# SCH_MONITORING-BANJIR_2024-11-29.net
KiCad netlist of a schematic drawn in EasyEDA
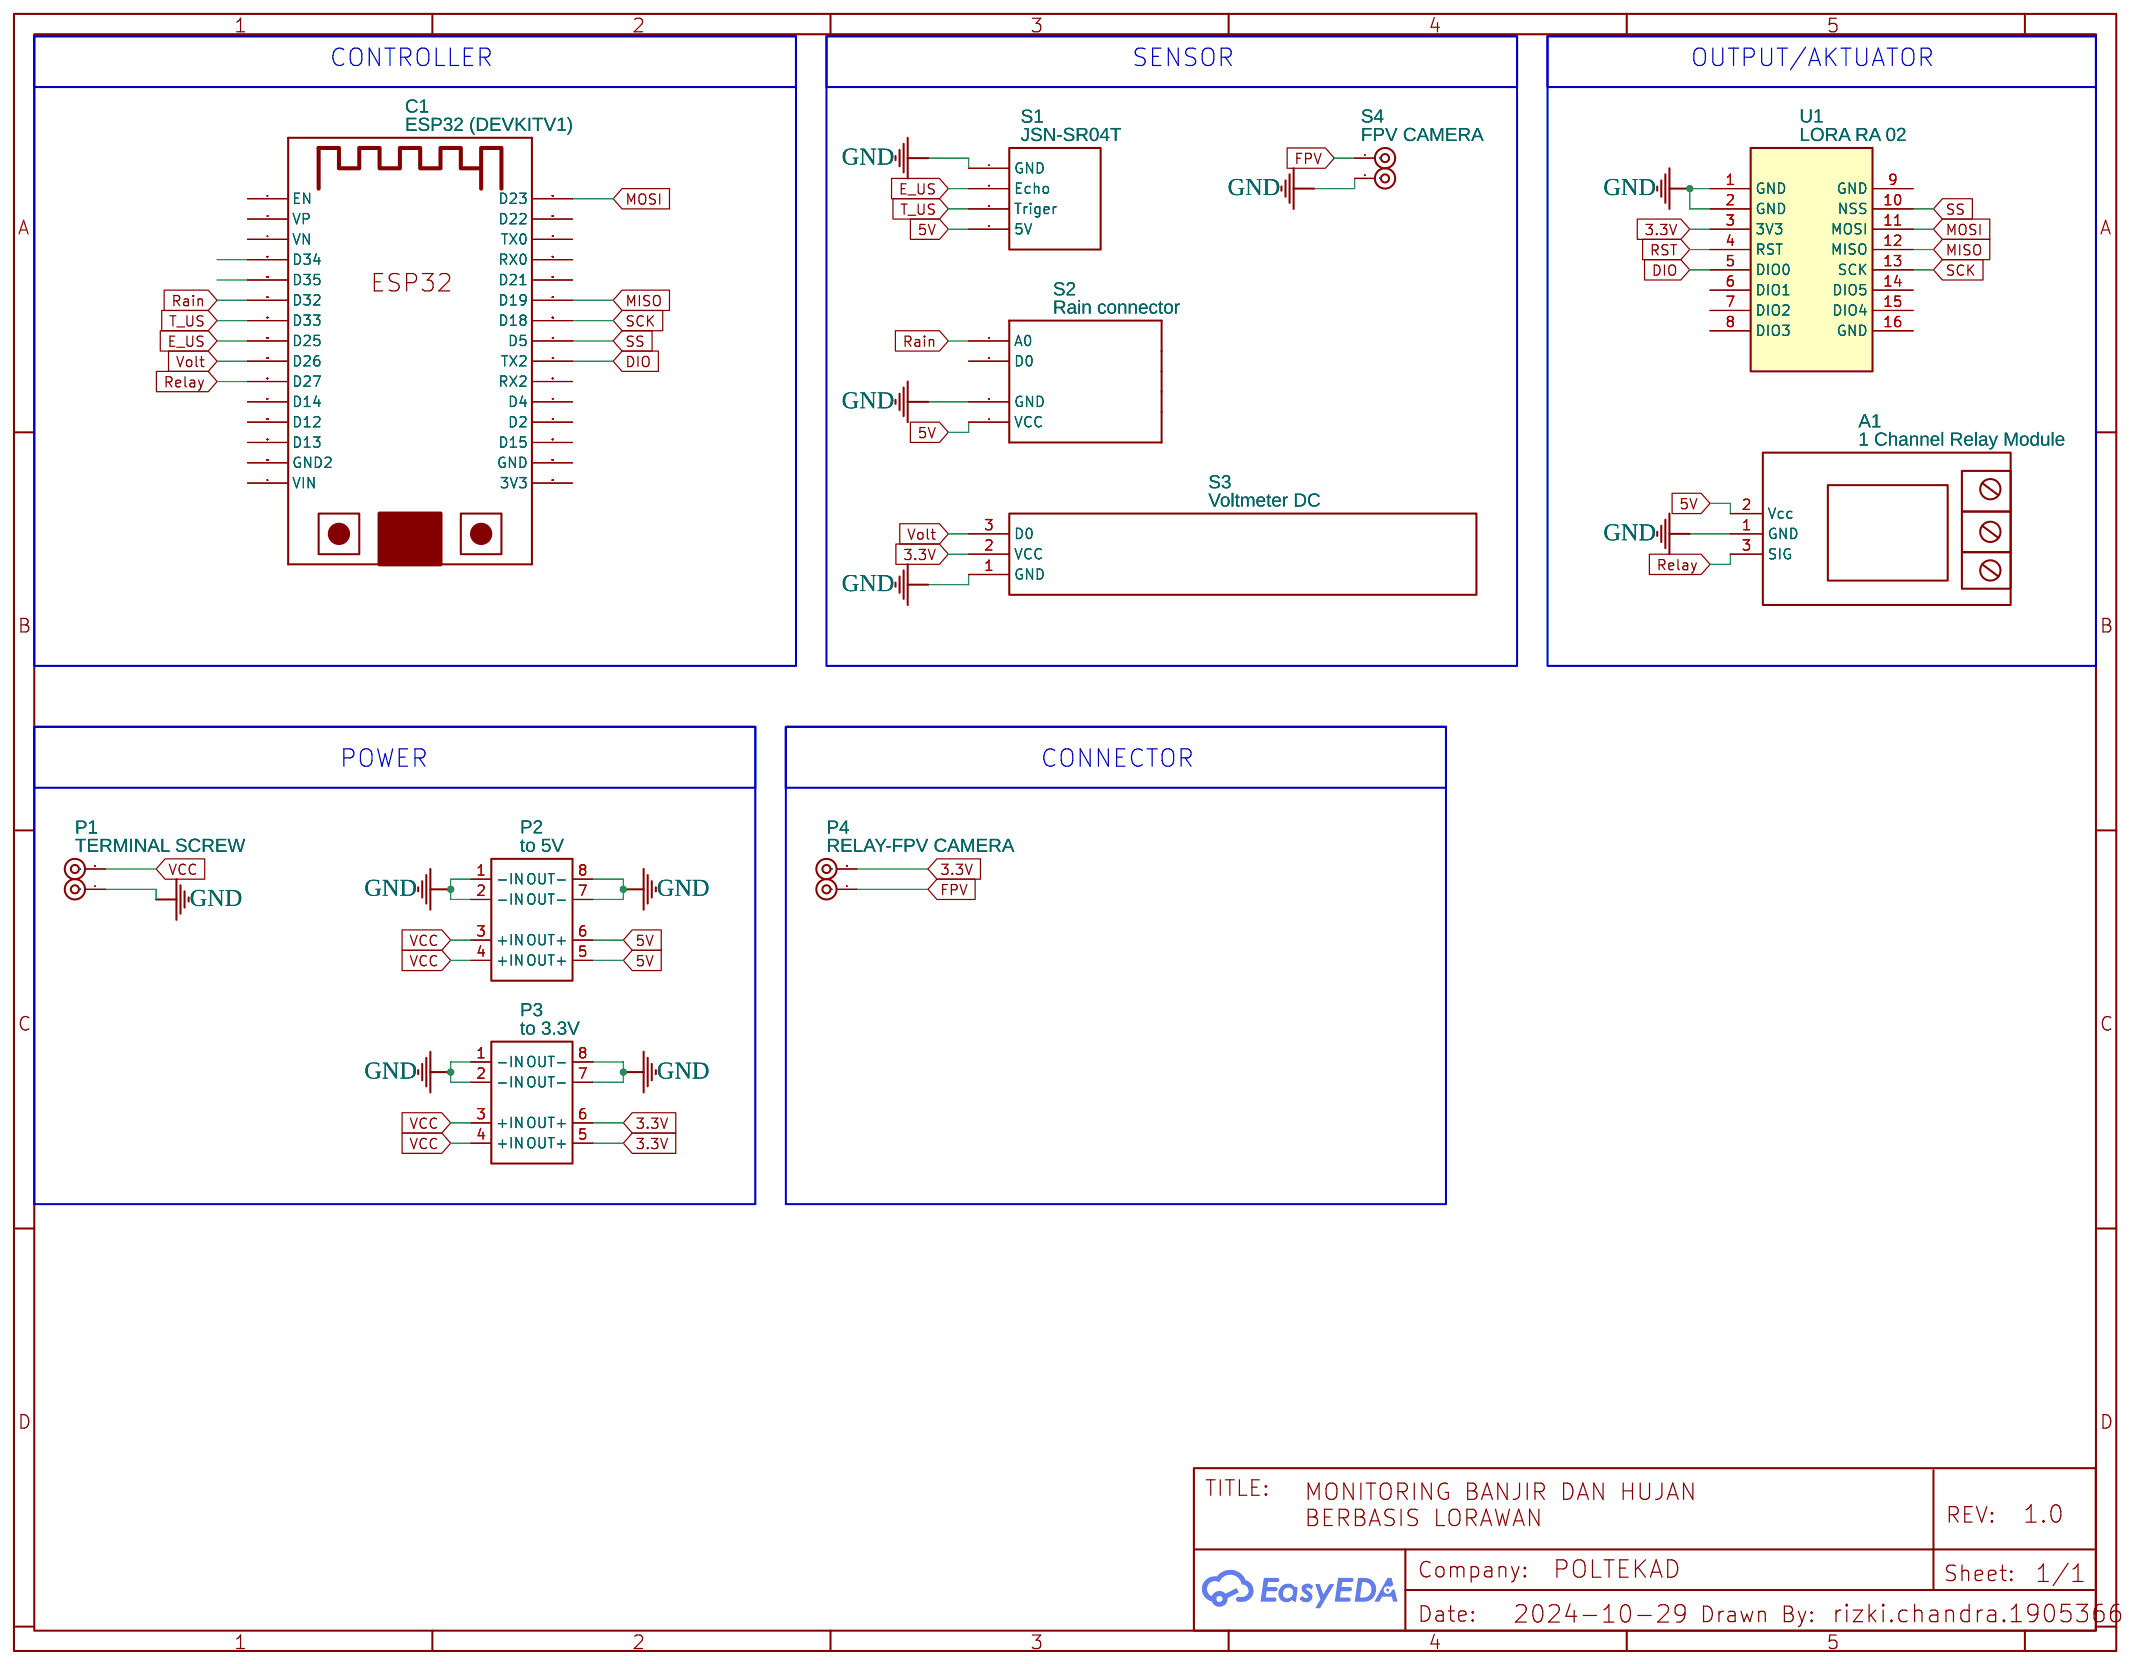
[diagram p0: schematic sheet]

(export (version "E")
  (design (tool "Eeschema 10.0.6"))
  (components
    (comp (ref "A1")
      (value "1 Channel Relay Module")
      (fields (field (name "Manufacturer Part") "1-Channel 5V Relay Module w/ Opto-isolator"))
      (libsource (lib "") (part "1 Channel Relay Module"))
    )
    (comp (ref "C1") (value "ESP32 (DEVKITV1)") (libsource (lib "") (part "ESP32-DEVKIT-V1-30PIN")))
    (comp (ref "P1") (value "TERMINAL SCREW") (libsource (lib "") (part "HEADER-MALE-2.54-1X2-2P_1")))
    (comp (ref "P2") (value "to 5V") (libsource (lib "") (part "MP1584EN-KZ")))
    (comp (ref "P3") (value "to 3.3V") (libsource (lib "") (part "MP1584EN-KZ")))
    (comp (ref "P4") (value "RELAY-FPV CAMERA") (libsource (lib "") (part "HEADER-MALE-2.54-1X2-2P_1")))
    (comp (ref "S1") (value "JSN-SR04T") (libsource (lib "") (part "JSN-SR04T")))
    (comp (ref "S2") (value "Rain connector") (libsource (lib "") (part "Rain connector")))
    (comp (ref "S3")
      (value "Voltmeter DC")
      (fields (field (name "Manufacturer Part") "Line_sensor"))
      (libsource (lib "") (part "TCRT5000 LINE SENSOR MODULE"))
    )
    (comp (ref "S4") (value "FPV CAMERA") (libsource (lib "") (part "HEADER-MALE-2.54-1X2-2P")))
    (comp (ref "U1")
      (value "LORA RA 02")
      (fields (field (name "Manufacturer Part") "Ra-02") (field (name "Manufacturer") "AiThinker"))
      (libsource (lib "") (part "LORA RA 02"))
    )
  )
  (nets
    (net (code "1") (name "3.3V") (class "Default")
      (node (ref "P3") (pin "5") (pinfunction "OUT+_5") (pintype "unspecified"))
      (node (ref "P3") (pin "6") (pinfunction "OUT+_6") (pintype "unspecified"))
      (node (ref "P4") (pin "2") (pinfunction "2_2") (pintype "unspecified"))
      (node (ref "S3") (pin "2") (pinfunction "VCC_2") (pintype "unspecified"))
      (node (ref "U1") (pin "3") (pinfunction "3V3_3") (pintype "unspecified"))
    )
    (net (code "2") (name "5V") (class "Default")
      (node (ref "A1") (pin "2") (pinfunction "Vcc_2") (pintype "input"))
      (node (ref "P2") (pin "5") (pinfunction "OUT+_5") (pintype "unspecified"))
      (node (ref "P2") (pin "6") (pinfunction "OUT+_6") (pintype "unspecified"))
      (node (ref "S1") (pin "1") (pinfunction "5V_1") (pintype "input"))
      (node (ref "S2") (pin "4") (pinfunction "VCC_4") (pintype "unspecified"))
    )
    (net (code "3") (name "DIO") (class "Default")
      (node (ref "C1") (pin "TX2") (pinfunction "TX2_TX2") (pintype "unspecified"))
      (node (ref "U1") (pin "5") (pinfunction "DIO0_5") (pintype "unspecified"))
    )
    (net (code "4") (name "E_US") (class "Default")
      (node (ref "C1") (pin "D25") (pinfunction "D25_D25") (pintype "unspecified"))
      (node (ref "S1") (pin "3") (pinfunction "Echo_3") (pintype "input"))
    )
    (net (code "5") (name "FPV") (class "Default")
      (node (ref "P4") (pin "1") (pinfunction "1_1") (pintype "unspecified"))
      (node (ref "S4") (pin "1") (pinfunction "1_1") (pintype "unspecified"))
    )
    (net (code "6") (name "GND") (class "Default")
      (node (ref "A1") (pin "1") (pinfunction "GND_1") (pintype "input"))
      (node (ref "P1") (pin "1") (pinfunction "1_1") (pintype "unspecified"))
      (node (ref "P2") (pin "1") (pinfunction "-IN_1") (pintype "unspecified"))
      (node (ref "P2") (pin "2") (pinfunction "-IN_2") (pintype "unspecified"))
      (node (ref "P2") (pin "7") (pinfunction "OUT-_7") (pintype "unspecified"))
      (node (ref "P2") (pin "8") (pinfunction "OUT-_8") (pintype "unspecified"))
      (node (ref "P3") (pin "1") (pinfunction "-IN_1") (pintype "unspecified"))
      (node (ref "P3") (pin "2") (pinfunction "-IN_2") (pintype "unspecified"))
      (node (ref "P3") (pin "7") (pinfunction "OUT-_7") (pintype "unspecified"))
      (node (ref "P3") (pin "8") (pinfunction "OUT-_8") (pintype "unspecified"))
      (node (ref "S1") (pin "4") (pinfunction "GND_4") (pintype "input"))
      (node (ref "S2") (pin "3") (pinfunction "GND_3") (pintype "unspecified"))
      (node (ref "S3") (pin "1") (pinfunction "GND_1") (pintype "unspecified"))
      (node (ref "S4") (pin "2") (pinfunction "2_2") (pintype "unspecified"))
      (node (ref "U1") (pin "1") (pinfunction "GND_1") (pintype "unspecified"))
      (node (ref "U1") (pin "2") (pinfunction "GND_2") (pintype "unspecified"))
    )
    (net (code "7") (name "MISO") (class "Default")
      (node (ref "C1") (pin "D19") (pinfunction "D19_D19") (pintype "unspecified"))
      (node (ref "U1") (pin "12") (pinfunction "MISO_12") (pintype "unspecified"))
    )
    (net (code "8") (name "MOSI") (class "Default")
      (node (ref "C1") (pin "D23") (pinfunction "D23_D23") (pintype "unspecified"))
      (node (ref "U1") (pin "11") (pinfunction "MOSI_11") (pintype "unspecified"))
    )
    (net (code "9") (name "RST") (class "Default")
      (node (ref "U1") (pin "4") (pinfunction "RST_4") (pintype "unspecified"))
    )
    (net (code "10") (name "Rain") (class "Default")
      (node (ref "C1") (pin "D32") (pinfunction "D32_D32") (pintype "unspecified"))
      (node (ref "S2") (pin "1") (pinfunction "A0_1") (pintype "unspecified"))
    )
    (net (code "11") (name "Relay") (class "Default")
      (node (ref "A1") (pin "3") (pinfunction "SIG_3") (pintype "input"))
      (node (ref "C1") (pin "D27") (pinfunction "D27_D27") (pintype "unspecified"))
    )
    (net (code "12") (name "SCK") (class "Default")
      (node (ref "C1") (pin "D18") (pinfunction "D18_D18") (pintype "unspecified"))
      (node (ref "U1") (pin "13") (pinfunction "SCK_13") (pintype "unspecified"))
    )
    (net (code "13") (name "SS") (class "Default")
      (node (ref "C1") (pin "D5") (pinfunction "D5_D5") (pintype "unspecified"))
      (node (ref "U1") (pin "10") (pinfunction "NSS_10") (pintype "unspecified"))
    )
    (net (code "14") (name "T_US") (class "Default")
      (node (ref "C1") (pin "D33") (pinfunction "D33_D33") (pintype "unspecified"))
      (node (ref "S1") (pin "2") (pinfunction "Triger_2") (pintype "input"))
    )
    (net (code "15") (name "VCC") (class "Default")
      (node (ref "P1") (pin "2") (pinfunction "2_2") (pintype "unspecified"))
      (node (ref "P2") (pin "3") (pinfunction "+IN_3") (pintype "unspecified"))
      (node (ref "P2") (pin "4") (pinfunction "+IN_4") (pintype "unspecified"))
      (node (ref "P3") (pin "3") (pinfunction "+IN_3") (pintype "unspecified"))
      (node (ref "P3") (pin "4") (pinfunction "+IN_4") (pintype "unspecified"))
    )
    (net (code "16") (name "Volt") (class "Default")
      (node (ref "C1") (pin "D26") (pinfunction "D26_D26") (pintype "unspecified"))
      (node (ref "S3") (pin "3") (pinfunction "D0_3") (pintype "unspecified"))
    )
    (net (code "17") (name "unconnected-(C1-Pad3V3)") (class "Default")
      (node (ref "C1") (pin "3V3") (pinfunction "3V3_3V3") (pintype "unspecified"))
    )
    (net (code "18") (name "unconnected-(C1-PadD2)") (class "Default")
      (node (ref "C1") (pin "D2") (pinfunction "D2_D2") (pintype "unspecified"))
    )
    (net (code "19") (name "unconnected-(C1-PadD4)") (class "Default")
      (node (ref "C1") (pin "D4") (pinfunction "D4_D4") (pintype "unspecified"))
    )
    (net (code "20") (name "unconnected-(C1-PadD12)") (class "Default")
      (node (ref "C1") (pin "D12") (pinfunction "D12_D12") (pintype "unspecified"))
    )
    (net (code "21") (name "unconnected-(C1-PadD13)") (class "Default")
      (node (ref "C1") (pin "D13") (pinfunction "D13_D13") (pintype "unspecified"))
    )
    (net (code "22") (name "unconnected-(C1-PadD14)") (class "Default")
      (node (ref "C1") (pin "D14") (pinfunction "D14_D14") (pintype "unspecified"))
    )
    (net (code "23") (name "unconnected-(C1-PadD15)") (class "Default")
      (node (ref "C1") (pin "D15") (pinfunction "D15_D15") (pintype "unspecified"))
    )
    (net (code "24") (name "unconnected-(C1-PadD21)") (class "Default")
      (node (ref "C1") (pin "D21") (pinfunction "D21_D21") (pintype "unspecified"))
    )
    (net (code "25") (name "unconnected-(C1-PadD22)") (class "Default")
      (node (ref "C1") (pin "D22") (pinfunction "D22_D22") (pintype "unspecified"))
    )
    (net (code "26") (name "unconnected-(C1-PadD34)") (class "Default")
      (node (ref "C1") (pin "D34") (pinfunction "D34_D34") (pintype "unspecified"))
    )
    (net (code "27") (name "unconnected-(C1-PadD35)") (class "Default")
      (node (ref "C1") (pin "D35") (pinfunction "D35_D35") (pintype "unspecified"))
    )
    (net (code "28") (name "unconnected-(C1-PadEN)") (class "Default")
      (node (ref "C1") (pin "EN") (pinfunction "EN_EN") (pintype "unspecified"))
    )
    (net (code "29") (name "unconnected-(C1-PadGND)") (class "Default")
      (node (ref "C1") (pin "GND") (pinfunction "GND_GND") (pintype "unspecified"))
    )
    (net (code "30") (name "unconnected-(C1-PadGND2)") (class "Default")
      (node (ref "C1") (pin "GND2") (pinfunction "GND2_GND2") (pintype "unspecified"))
    )
    (net (code "31") (name "unconnected-(C1-PadRX0)") (class "Default")
      (node (ref "C1") (pin "RX0") (pinfunction "RX0_RX0") (pintype "unspecified"))
    )
    (net (code "32") (name "unconnected-(C1-PadRX2)") (class "Default")
      (node (ref "C1") (pin "RX2") (pinfunction "RX2_RX2") (pintype "unspecified"))
    )
    (net (code "33") (name "unconnected-(C1-PadTX0)") (class "Default")
      (node (ref "C1") (pin "TX0") (pinfunction "TX0_TX0") (pintype "unspecified"))
    )
    (net (code "34") (name "unconnected-(C1-PadVIN)") (class "Default")
      (node (ref "C1") (pin "VIN") (pinfunction "VIN_VIN") (pintype "unspecified"))
    )
    (net (code "35") (name "unconnected-(C1-PadVN)") (class "Default")
      (node (ref "C1") (pin "VN") (pinfunction "VN_VN") (pintype "unspecified"))
    )
    (net (code "36") (name "unconnected-(C1-PadVP)") (class "Default")
      (node (ref "C1") (pin "VP") (pinfunction "VP_VP") (pintype "unspecified"))
    )
    (net (code "37") (name "unconnected-(S2-D0-Pad2)") (class "Default")
      (node (ref "S2") (pin "2") (pinfunction "D0_2") (pintype "unspecified"))
    )
    (net (code "38") (name "unconnected-(U1-DIO1-Pad6)") (class "Default")
      (node (ref "U1") (pin "6") (pinfunction "DIO1_6") (pintype "unspecified"))
    )
    (net (code "39") (name "unconnected-(U1-DIO2-Pad7)") (class "Default")
      (node (ref "U1") (pin "7") (pinfunction "DIO2_7") (pintype "unspecified"))
    )
    (net (code "40") (name "unconnected-(U1-DIO3-Pad8)") (class "Default")
      (node (ref "U1") (pin "8") (pinfunction "DIO3_8") (pintype "unspecified"))
    )
    (net (code "41") (name "unconnected-(U1-DIO4-Pad15)") (class "Default")
      (node (ref "U1") (pin "15") (pinfunction "DIO4_15") (pintype "unspecified"))
    )
    (net (code "42") (name "unconnected-(U1-DIO5-Pad14)") (class "Default")
      (node (ref "U1") (pin "14") (pinfunction "DIO5_14") (pintype "unspecified"))
    )
    (net (code "43") (name "unconnected-(U1-GND-Pad9)") (class "Default")
      (node (ref "U1") (pin "9") (pinfunction "GND_9") (pintype "unspecified"))
    )
    (net (code "44") (name "unconnected-(U1-GND-Pad16)") (class "Default")
      (node (ref "U1") (pin "16") (pinfunction "GND_16") (pintype "unspecified"))
    )
  )
)
